# ESP32_MCU.net
KiCad netlist of a schematic drawn in Altium Designer
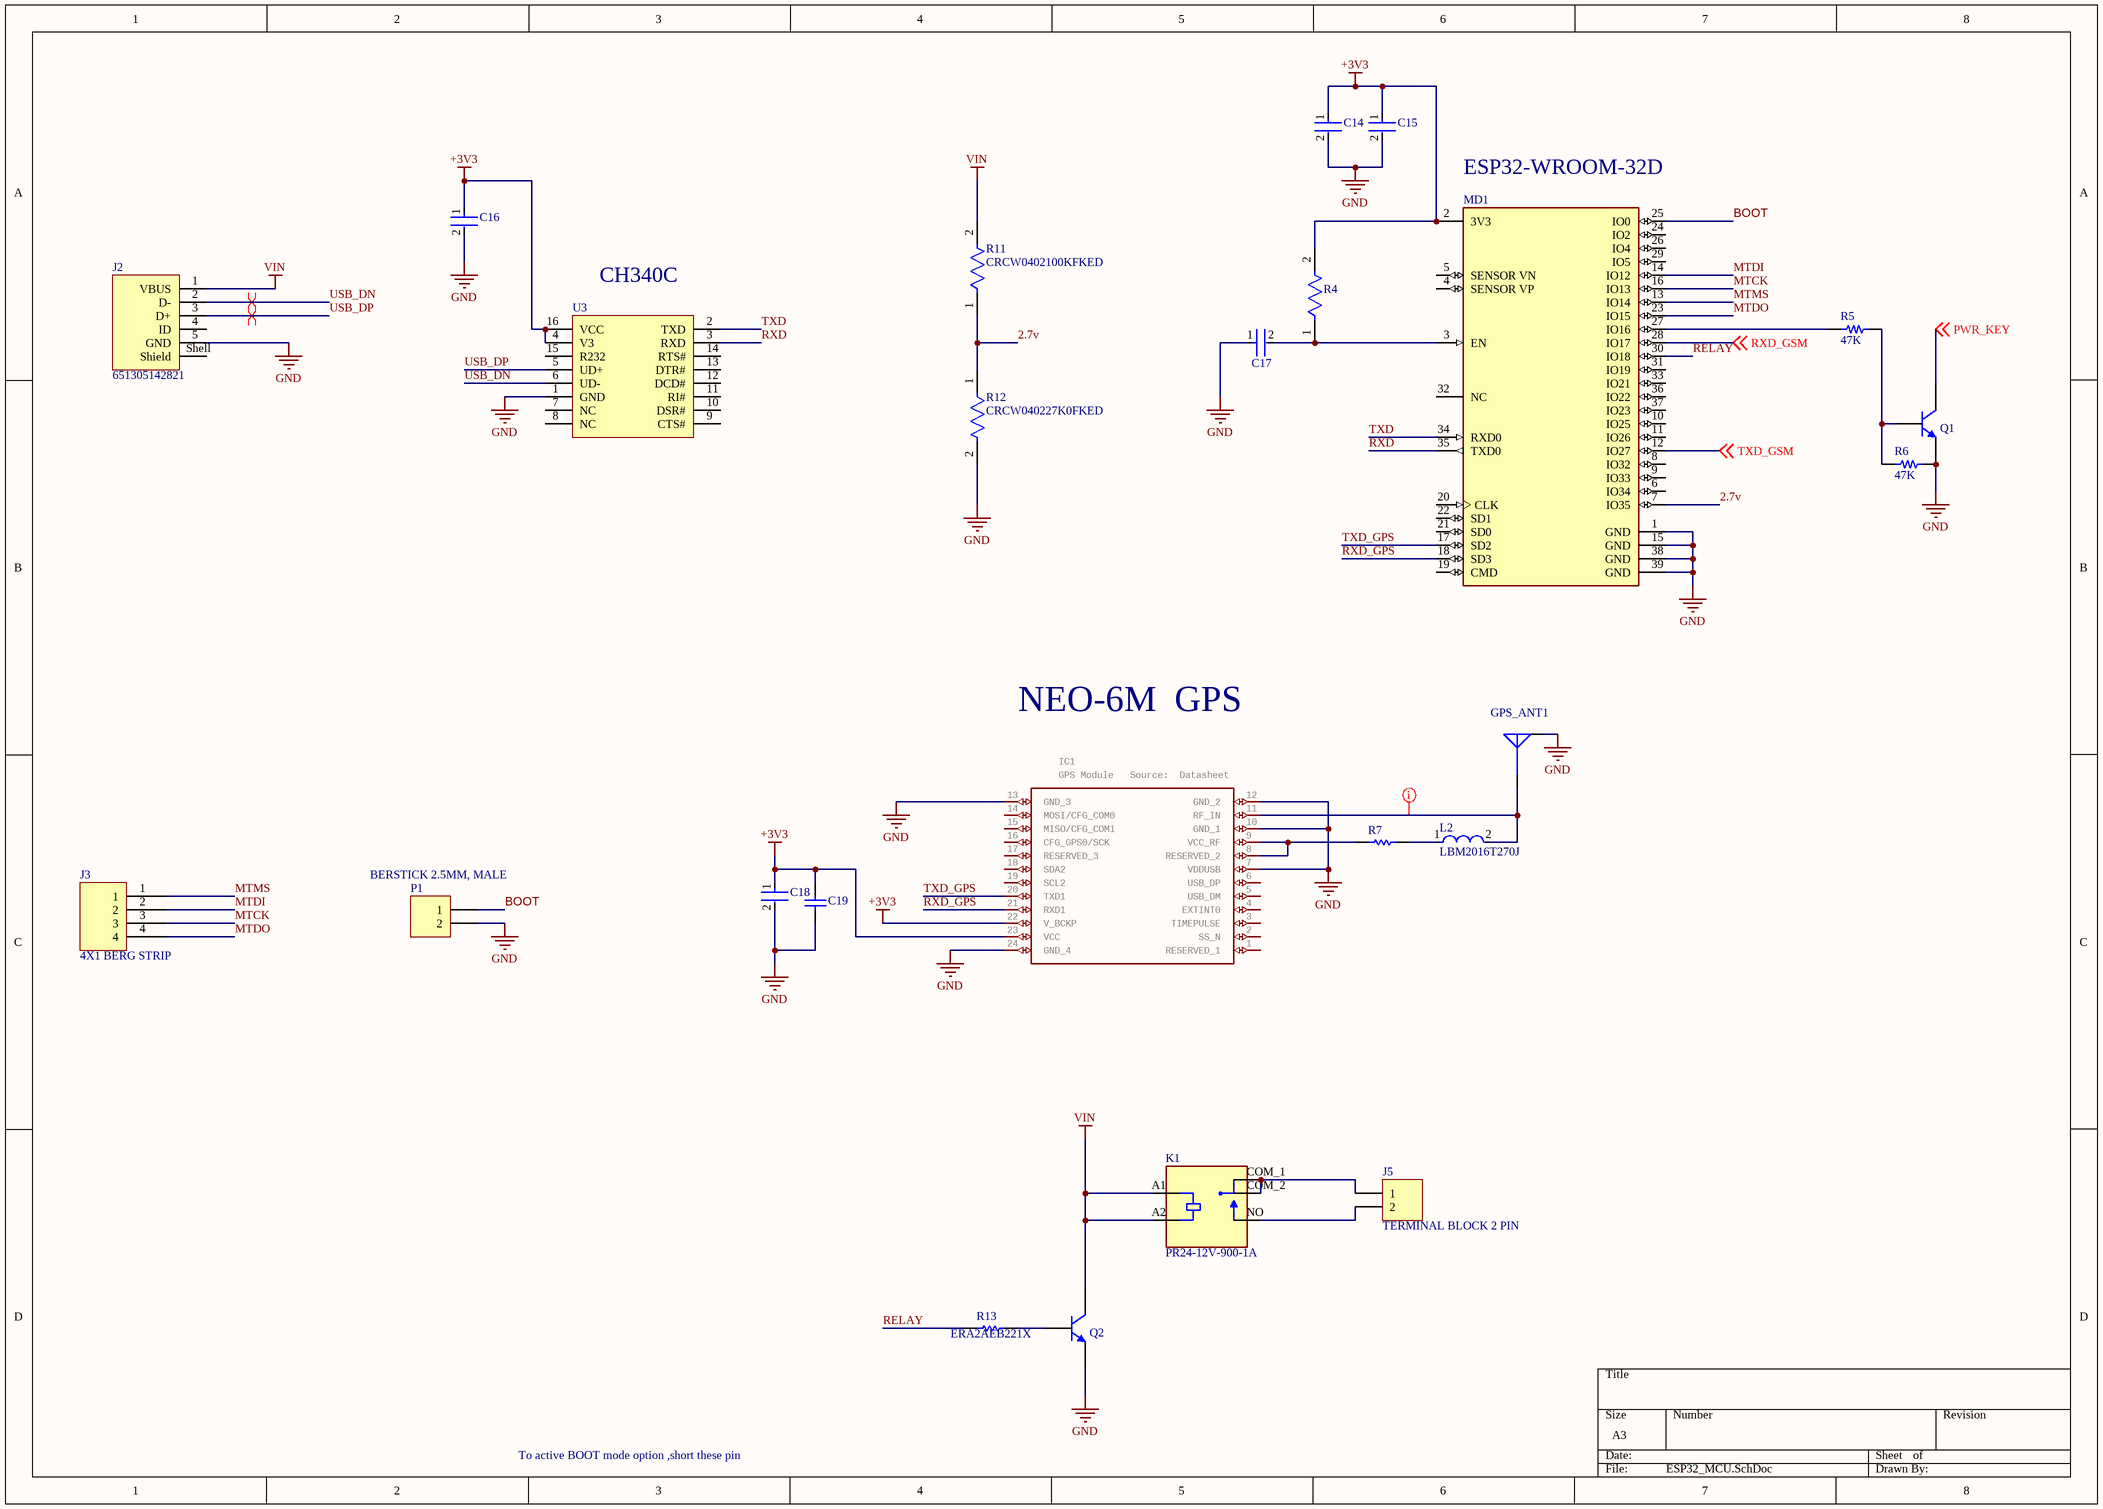
[diagram p0: ESP32_MCU.SchDoc]

(export (version "E")
  (design (tool "Eeschema 10.0.6"))
  (components
    (comp (ref "C14")
      (value "C0402C104K8RACTU")
      (footprint "FP-C0402-BB-MFG")
      (description "CAP CER 0.1UF 10V X7R 0402")
      (fields
        (field (name "OCTOPART") "https://octopart.com/c0402c104k8ractu-kemet-106349")
        (field (name "TOLERANCE") "0.1")
      )
      (libsource (lib "Altium Content Vault") (part "b4654b650e69147ec39a6b967a45e02"))
    )
    (comp (ref "C15")
      (value "C0402C106M9PACTU")
      (footprint "FP-C0402C106M9PACTU-MFG")
      (description "CAP CER 10UF 6.3V X5R 0402")
      (fields (field (name "TOLERANCE") "20%"))
      (libsource (lib "Altium Content Vault") (part "b4654b650e69147ec39a6b967a45e02"))
    )
    (comp (ref "C16")
      (value "C0402C104K8RACTU")
      (footprint "FP-C0402-BB-MFG")
      (description "CAP CER 0.1UF 10V X7R 0402")
      (fields
        (field (name "OCTOPART") "https://octopart.com/c0402c104k8ractu-kemet-106349")
        (field (name "TOLERANCE") "0.1")
      )
      (libsource (lib "Altium Content Vault") (part "b4654b650e69147ec39a6b967a45e02"))
    )
    (comp (ref "C17")
      (value "CC0402KRX5R5BB105")
      (footprint "FP-CC0402-MFG")
      (description "CAP CER 1UF 6.3V X5R 0402")
      (fields
        (field (name "MANUFACTURER") "YAGEO")
        (field (name "OCTOPART") "https://octopart.com/cc0402krx5r5bb105-yageo-42244618")
      )
      (libsource (lib "Altium Content Vault") (part "11868f565c42a9108669ba33697ecf6"))
    )
    (comp (ref "C18")
      (value "C0402C104K8RACTU")
      (footprint "FP-C0402-BB-MFG")
      (description "CAP CER 0.1UF 10V X7R 0402")
      (fields
        (field (name "OCTOPART") "https://octopart.com/c0402c104k8ractu-kemet-106349")
        (field (name "TOLERANCE") "0.1")
      )
      (libsource (lib "Altium Content Vault") (part "b4654b650e69147ec39a6b967a45e02"))
    )
    (comp (ref "C19")
      (value "C0402C475M7PACTU")
      (footprint "CAPC1005X60X30ML05T10")
      (fields (field (name "MANUFACTURER") "Kemet"))
      (libsource (lib "Altium Content Vault") (part "CAP"))
    )
    (comp (ref "GPS_ANT1")
      (value "UFL")
      (footprint "MOLEX SD-734120110")
      (fields (field (name "PARTNUMBER") "MOLEX SD-734120110"))
      (libsource (lib "GSM Shutter lock system") (part "UFL MOLEX SD-734120110"))
    )
    (comp (ref "IC1")
      (value "GPS Module   Source:  Datasheet")
      (footprint "NEO6M0001")
      (fields (field (name "MANUFACTURER_PART_NUMBER") "NEO-6M-0-001"))
      (libsource (lib "NEO-6M-0-001") (part "NEO-6M-0-001"))
    )
    (comp (ref "J2")
      (value "651305142821")
      (footprint "651305142821")
      (libsource (lib "Altium Content Vault") (part "Mini USB 2.0_Type AB_Receptacle_1 Port"))
    )
    (comp (ref "J3")
      (value "4X1 BERG STRIP")
      (footprint "CON4_100_40D72_TH_ST_MALE")
      (description "4 Pins, 1 Row 2.54mm Pitch, Straight bergstrip, Male")
      (fields (field (name "MANUFACTURER") "NA"))
      (libsource (lib "ESTEEMPCBLIB") (part "CON-BS-PLG_4X1-100-ST-TH"))
    )
    (comp (ref "J5")
      (value "TERMINAL BLOCK 2 PIN")
      (footprint "CON2_P196_1729128_TH_ST")
      (description "2 Pins, 1 Row 5mm Pitch, straight Connector, male")
      (fields
        (field (name "MANUFACTURER") "Phoenix Contact")
        (field (name "MANUFACTURER PART NUMBER") "MKDSN1,5/2")
      )
      (libsource (lib "ESTEEMPCBLIB") (part "CON-TB_2X1-196-ST-TH"))
    )
    (comp (ref "K1")
      (value "PR24-12V-900-1A")
      (footprint "RELAY_PR24-12V-900-1A")
      (description "27.4 x 31.8 x 20 mm, 12 V, 40 A, SPST (1 Form A), Power Relay")
      (fields (field (name "MF") "CUI Devices"))
      (libsource (lib "PR24-12V-900-1A") (part "PR24-12V-900-1A"))
    )
    (comp (ref "L2")
      (value "LBM2016T270J")
      (footprint "FP-LBM2016-1_6-0_2-IPC_C")
      (description "SMD Inductors 27uH ±5% 0.13A 4.16Ω 0806")
      (fields (field (name "TOLERANCE") "5%"))
      (libsource (lib "Altium Content Vault") (part "725321dda6339637d4d059423bc1c3c"))
    )
    (comp (ref "MD1")
      (value "ESP32-WROOM-32D")
      (footprint "FP-ESP32-WROOM-32D-MFG")
      (description "WIFI MODULE 32MBITS SPI FLASH")
      (fields
        (field (name "OCTOPART") "https://octopart.com/esp32-wroom-32d-espressif+systems-91040050")
        (field (name "MANUFACTURER") "Espressif Systems")
      )
      (libsource (lib "Altium Content Vault") (part "a031a76f8c27026a7a7f4657ff233a3"))
    )
    (comp (ref "P1")
      (value "BERSTICK 2.5MM, MALE")
      (footprint "CON2_100_43D62_TH_ST")
      (description "2 Pins, 1 Row 2.54mm Pitch, Straight bergstrip, Male")
      (fields (field (name "MANUFACTURER PART NUMBER") "NA") (field (name "MANUFACTURER") "Samtec"))
      (libsource (lib "ESTEEMPCBLIB") (part "CON-BS-PLG_2X1-100-ST-TH"))
    )
    (comp (ref "Q1")
      (value "8050")
      (footprint "SOT-23-3 2.9X2.4MM P0.95MM")
      (description "Bipolar (BJT) Transistor NPN 25V 1.5A 100MHz 625mW Surface Mount SOT-23")
      (fields (field (name "PARTNUMBER") "MMSS8050-L-TP"))
      (libsource (lib "Transistor") (part "MMSS8050 (SMD)"))
    )
    (comp (ref "Q2")
      (value "8050")
      (footprint "SOT-23-3 2.9X2.4MM P0.95MM")
      (description "Bipolar (BJT) Transistor NPN 25V 1.5A 100MHz 625mW Surface Mount SOT-23")
      (fields (field (name "PARTNUMBER") "MMSS8050-L-TP"))
      (libsource (lib "Transistor") (part "MMSS8050 (SMD)"))
    )
    (comp (ref "R4")
      (value "CRCW040210K0JNED")
      (footprint "FP-CRCW0402-e3-IPC_B")
      (description "RES Thick Film, 10kΩ, 5%, 0.063W, 200ppm/°C, 0402")
      (fields (field (name "TOLERANCE") "5%"))
      (libsource (lib "Altium Content Vault") (part "1029c3af85768c4190bb7ad29bc67b5"))
    )
    (comp (ref "R5")
      (value "47K")
      (footprint "RES 0603_1608")
      (description "SMT Resistor")
      (libsource (lib "Resistor") (part "Res 0603"))
    )
    (comp (ref "R6")
      (value "47K")
      (footprint "RES 0603_1608")
      (description "SMT Resistor")
      (libsource (lib "Resistor") (part "Res 0603"))
    )
    (comp (ref "R7")
      (value "CRCW040222R0FKED")
      (footprint "RESC1005X40X25LL05T05")
      (fields (field (name "MANUFACTURER") "Vishay Dale"))
      (libsource (lib "Altium Content Vault") (part "RES"))
    )
    (comp (ref "R11")
      (value "CRCW0402100KFKED")
      (footprint "FP-CRCW0402-e3-IPC_C")
      (description "RES Thick Film, 100kΩ, 1%, 0.063W, 100ppm/°C, 0402")
      (fields (field (name "TOLERANCE") "1%"))
      (libsource (lib "Altium Content Vault") (part "1029c3af85768c4190bb7ad29bc67b5"))
    )
    (comp (ref "R12")
      (value "CRCW040227K0FKED")
      (footprint "FP-CRCW0402-e3-IPC_A")
      (description "RES Thick Film, 27kΩ, 1%, 0.063W, 100ppm/°C, 0402")
      (fields (field (name "TOLERANCE") "1%"))
      (libsource (lib "Altium Content Vault") (part "1029c3af85768c4190bb7ad29bc67b5"))
    )
    (comp (ref "R13")
      (value "ERA2AEB221X")
      (footprint "RESC1005X40X25LL10T10")
      (fields (field (name "MANUFACTURER") "Panasonic"))
      (libsource (lib "Altium Content Vault") (part "RES"))
    )
    (comp (ref "U3")
      (value "CH340C")
      (footprint "SOIC16_50_284_25X90_SMT")
      (description "USB Bridge, USB to UART USB 2.0 UART Interface")
      (fields (field (name "MANUFACTURER") "Olimex"))
      (libsource (lib "ESTEEMPCBLIB") (part "IC_CH340C"))
    )
  )
  (nets
    (net (code "1") (name "+3V3") (class "Default")
      (node (ref "C14") (pin "1") (pinfunction "1_1") (pintype "passive"))
      (node (ref "C15") (pin "1") (pinfunction "1_1") (pintype "passive"))
      (node (ref "C16") (pin "1") (pinfunction "1_1") (pintype "passive"))
      (node (ref "C18") (pin "1") (pinfunction "1_1") (pintype "passive"))
      (node (ref "C19") (pin "2") (pinfunction "2_2") (pintype "passive"))
      (node (ref "IC1") (pin "22") (pinfunction "V_BCKP_22") (pintype "bidirectional"))
      (node (ref "IC1") (pin "23") (pinfunction "VCC_23") (pintype "bidirectional"))
      (node (ref "MD1") (pin "2") (pinfunction "3V3_2") (pintype "power_in"))
      (node (ref "R4") (pin "2") (pinfunction "2_2") (pintype "passive"))
      (node (ref "U3") (pin "16") (pinfunction "VCC_16") (pintype "passive"))
      (node (ref "U3") (pin "4") (pinfunction "V3_4") (pintype "passive"))
    )
    (net (code "2") (name "/2.7v") (class "Default")
      (node (ref "MD1") (pin "7") (pinfunction "IO35_7") (pintype "bidirectional"))
      (node (ref "R11") (pin "1") (pinfunction "1_1") (pintype "passive"))
      (node (ref "R12") (pin "1") (pinfunction "1_1") (pintype "passive"))
    )
    (net (code "3") (name "/BOOT") (class "Default")
      (node (ref "MD1") (pin "25") (pinfunction "IO0_25") (pintype "bidirectional"))
      (node (ref "P1") (pin "1") (pinfunction "1_1") (pintype "passive"))
    )
    (net (code "4") (name "/MTCK") (class "Default")
      (node (ref "J3") (pin "3") (pinfunction "3_3") (pintype "passive"))
      (node (ref "MD1") (pin "16") (pinfunction "IO13_16") (pintype "bidirectional"))
    )
    (net (code "5") (name "/MTDI") (class "Default")
      (node (ref "J3") (pin "2") (pinfunction "2_2") (pintype "passive"))
      (node (ref "MD1") (pin "14") (pinfunction "IO12_14") (pintype "bidirectional"))
    )
    (net (code "6") (name "/MTDO") (class "Default")
      (node (ref "J3") (pin "4") (pinfunction "4_4") (pintype "passive"))
      (node (ref "MD1") (pin "23") (pinfunction "IO15_23") (pintype "bidirectional"))
    )
    (net (code "7") (name "/MTMS") (class "Default")
      (node (ref "J3") (pin "1") (pinfunction "1_1") (pintype "passive"))
      (node (ref "MD1") (pin "13") (pinfunction "IO14_13") (pintype "bidirectional"))
    )
    (net (code "8") (name "/RELAY") (class "Default")
      (node (ref "MD1") (pin "30") (pinfunction "IO18_30") (pintype "bidirectional"))
      (node (ref "R13") (pin "1") (pinfunction "1_1") (pintype "passive"))
    )
    (net (code "9") (name "/RXD") (class "Default")
      (node (ref "MD1") (pin "35") (pinfunction "TXD0_35") (pintype "output"))
      (node (ref "U3") (pin "3") (pinfunction "RXD_3") (pintype "passive"))
    )
    (net (code "10") (name "/RXD_GPS") (class "Default")
      (node (ref "IC1") (pin "21") (pinfunction "RXD1_21") (pintype "bidirectional"))
      (node (ref "MD1") (pin "18") (pinfunction "SD3_18") (pintype "bidirectional"))
    )
    (net (code "11") (name "/TXD") (class "Default")
      (node (ref "MD1") (pin "34") (pinfunction "RXD0_34") (pintype "input"))
      (node (ref "U3") (pin "2") (pinfunction "TXD_2") (pintype "passive"))
    )
    (net (code "12") (name "/TXD_GPS") (class "Default")
      (node (ref "IC1") (pin "20") (pinfunction "TXD1_20") (pintype "bidirectional"))
      (node (ref "MD1") (pin "17") (pinfunction "SD2_17") (pintype "bidirectional"))
    )
    (net (code "13") (name "/USB_DN") (class "Default")
      (node (ref "J2") (pin "2") (pinfunction "D-_2") (pintype "passive"))
      (node (ref "U3") (pin "6") (pinfunction "UD-_6") (pintype "passive"))
    )
    (net (code "14") (name "/USB_DP") (class "Default")
      (node (ref "J2") (pin "3") (pinfunction "D+_3") (pintype "passive"))
      (node (ref "U3") (pin "5") (pinfunction "UD+_5") (pintype "passive"))
    )
    (net (code "15") (name "GND") (class "Default")
      (node (ref "C14") (pin "2") (pinfunction "2_2") (pintype "passive"))
      (node (ref "C15") (pin "2") (pinfunction "2_2") (pintype "passive"))
      (node (ref "C16") (pin "2") (pinfunction "2_2") (pintype "passive"))
      (node (ref "C17") (pin "1") (pinfunction "1_1") (pintype "passive"))
      (node (ref "C18") (pin "2") (pinfunction "2_2") (pintype "passive"))
      (node (ref "C19") (pin "1") (pinfunction "1_1") (pintype "passive"))
      (node (ref "GPS_ANT1") (pin "G") (pinfunction "G_G") (pintype "passive"))
      (node (ref "IC1") (pin "10") (pinfunction "GND_1_10") (pintype "bidirectional"))
      (node (ref "IC1") (pin "12") (pinfunction "GND_2_12") (pintype "bidirectional"))
      (node (ref "IC1") (pin "13") (pinfunction "GND_3_13") (pintype "bidirectional"))
      (node (ref "IC1") (pin "24") (pinfunction "GND_4_24") (pintype "bidirectional"))
      (node (ref "IC1") (pin "7") (pinfunction "VDDUSB_7") (pintype "bidirectional"))
      (node (ref "J2") (pin "5") (pinfunction "GND_5") (pintype "passive"))
      (node (ref "MD1") (pin "1") (pinfunction "GND_1") (pintype "power_in"))
      (node (ref "MD1") (pin "15") (pinfunction "GND_15") (pintype "power_in"))
      (node (ref "MD1") (pin "38") (pinfunction "GND_38") (pintype "power_in"))
      (node (ref "MD1") (pin "39") (pinfunction "GND_39") (pintype "power_in"))
      (node (ref "P1") (pin "2") (pinfunction "2_2") (pintype "passive"))
      (node (ref "Q1") (pin "2") (pinfunction "E_2") (pintype "passive"))
      (node (ref "Q2") (pin "2") (pinfunction "E_2") (pintype "passive"))
      (node (ref "R12") (pin "2") (pinfunction "2_2") (pintype "passive"))
      (node (ref "R6") (pin "1") (pinfunction "1_1") (pintype "passive"))
      (node (ref "U3") (pin "1") (pinfunction "GND_1") (pintype "passive"))
    )
    (net (code "16") (name "Net-(IC1-RESERVED_2)") (class "Default")
      (node (ref "IC1") (pin "8") (pinfunction "RESERVED_2_8") (pintype "bidirectional"))
      (node (ref "IC1") (pin "9") (pinfunction "VCC_RF_9") (pintype "bidirectional"))
      (node (ref "R7") (pin "1") (pinfunction "1_1") (pintype "passive"))
    )
    (net (code "17") (name "Net-(IC1-RF_IN)") (class "Default")
      (node (ref "GPS_ANT1") (pin "S") (pinfunction "S_S") (pintype "passive"))
      (node (ref "IC1") (pin "11") (pinfunction "RF_IN_11") (pintype "bidirectional"))
      (node (ref "L2") (pin "2") (pinfunction "2_2") (pintype "passive"))
    )
    (net (code "18") (name "Net-(J5-Pad2)") (class "Default")
      (node (ref "J5") (pin "2") (pinfunction "2_2") (pintype "passive"))
      (node (ref "K1") (pin "NO") (pinfunction "NO_NO") (pintype "passive"))
    )
    (net (code "19") (name "Net-(K1-COM1)") (class "Default")
      (node (ref "J5") (pin "1") (pinfunction "1_1") (pintype "passive"))
      (node (ref "K1") (pin "COM_1") (pinfunction "COM1_COM_1") (pintype "passive"))
      (node (ref "K1") (pin "COM_2") (pinfunction "COM2_COM_2") (pintype "passive"))
    )
    (net (code "20") (name "Net-(L2-Pad1)") (class "Default")
      (node (ref "L2") (pin "1") (pinfunction "1_1") (pintype "passive"))
      (node (ref "R7") (pin "2") (pinfunction "2_2") (pintype "passive"))
    )
    (net (code "21") (name "Net-(MD1-EN)") (class "Default")
      (node (ref "C17") (pin "2") (pinfunction "2_2") (pintype "passive"))
      (node (ref "MD1") (pin "3") (pinfunction "EN_3") (pintype "input"))
      (node (ref "R4") (pin "1") (pinfunction "1_1") (pintype "passive"))
    )
    (net (code "22") (name "Net-(MD1-IO16)") (class "Default")
      (node (ref "MD1") (pin "27") (pinfunction "IO16_27") (pintype "bidirectional"))
      (node (ref "R5") (pin "2") (pinfunction "2_2") (pintype "passive"))
    )
    (net (code "23") (name "Net-(Q1-B)") (class "Default")
      (node (ref "Q1") (pin "1") (pinfunction "B_1") (pintype "passive"))
      (node (ref "R5") (pin "1") (pinfunction "1_1") (pintype "passive"))
      (node (ref "R6") (pin "2") (pinfunction "2_2") (pintype "passive"))
    )
    (net (code "24") (name "Net-(Q2-B)") (class "Default")
      (node (ref "Q2") (pin "1") (pinfunction "B_1") (pintype "passive"))
      (node (ref "R13") (pin "2") (pinfunction "2_2") (pintype "passive"))
    )
    (net (code "25") (name "PWR_KEY") (class "Default")
      (node (ref "Q1") (pin "3") (pinfunction "C_3") (pintype "passive"))
    )
    (net (code "26") (name "RXD_GSM") (class "Default")
      (node (ref "MD1") (pin "28") (pinfunction "IO17_28") (pintype "bidirectional"))
    )
    (net (code "27") (name "TXD_GSM") (class "Default")
      (node (ref "MD1") (pin "12") (pinfunction "IO27_12") (pintype "bidirectional"))
    )
    (net (code "28") (name "VIN") (class "Default")
      (node (ref "J2") (pin "1") (pinfunction "VBUS_1") (pintype "passive"))
      (node (ref "K1") (pin "A1") (pinfunction "COIL1_A1") (pintype "passive"))
      (node (ref "K1") (pin "A2") (pinfunction "COIL2_A2") (pintype "passive"))
      (node (ref "Q2") (pin "3") (pinfunction "C_3") (pintype "passive"))
      (node (ref "R11") (pin "2") (pinfunction "2_2") (pintype "passive"))
    )
    (net (code "29") (name "unconnected-(IC1-CFG_GPS0{slash}SCK-Pad16)") (class "Default")
      (node (ref "IC1") (pin "16") (pinfunction "CFG_GPS0/SCK_16") (pintype "bidirectional"))
    )
    (net (code "30") (name "unconnected-(IC1-EXTINT0-Pad4)") (class "Default")
      (node (ref "IC1") (pin "4") (pinfunction "EXTINT0_4") (pintype "bidirectional"))
    )
    (net (code "31") (name "unconnected-(IC1-MISO{slash}CFG_COM1-Pad15)") (class "Default")
      (node (ref "IC1") (pin "15") (pinfunction "MISO/CFG_COM1_15") (pintype "bidirectional"))
    )
    (net (code "32") (name "unconnected-(IC1-MOSI{slash}CFG_COM0-Pad14)") (class "Default")
      (node (ref "IC1") (pin "14") (pinfunction "MOSI/CFG_COM0_14") (pintype "bidirectional"))
    )
    (net (code "33") (name "unconnected-(IC1-RESERVED_1-Pad1)") (class "Default")
      (node (ref "IC1") (pin "1") (pinfunction "RESERVED_1_1") (pintype "bidirectional"))
    )
    (net (code "34") (name "unconnected-(IC1-RESERVED_3-Pad17)") (class "Default")
      (node (ref "IC1") (pin "17") (pinfunction "RESERVED_3_17") (pintype "bidirectional"))
    )
    (net (code "35") (name "unconnected-(IC1-SCL2-Pad19)") (class "Default")
      (node (ref "IC1") (pin "19") (pinfunction "SCL2_19") (pintype "bidirectional"))
    )
    (net (code "36") (name "unconnected-(IC1-SDA2-Pad18)") (class "Default")
      (node (ref "IC1") (pin "18") (pinfunction "SDA2_18") (pintype "bidirectional"))
    )
    (net (code "37") (name "unconnected-(IC1-SS_N-Pad2)") (class "Default")
      (node (ref "IC1") (pin "2") (pinfunction "SS_N_2") (pintype "bidirectional"))
    )
    (net (code "38") (name "unconnected-(IC1-TIMEPULSE-Pad3)") (class "Default")
      (node (ref "IC1") (pin "3") (pinfunction "TIMEPULSE_3") (pintype "bidirectional"))
    )
    (net (code "39") (name "unconnected-(IC1-USB_DM-Pad5)") (class "Default")
      (node (ref "IC1") (pin "5") (pinfunction "USB_DM_5") (pintype "bidirectional"))
    )
    (net (code "40") (name "unconnected-(IC1-USB_DP-Pad6)") (class "Default")
      (node (ref "IC1") (pin "6") (pinfunction "USB_DP_6") (pintype "bidirectional"))
    )
    (net (code "41") (name "unconnected-(J2-ID-Pad4)") (class "Default")
      (node (ref "J2") (pin "4") (pinfunction "ID_4") (pintype "passive"))
    )
    (net (code "42") (name "unconnected-(J2-Shield-PadShell)") (class "Default")
      (node (ref "J2") (pin "Shell") (pinfunction "Shield_Shell") (pintype "passive"))
    )
    (net (code "43") (name "unconnected-(MD1-CLK-Pad20)") (class "Default")
      (node (ref "MD1") (pin "20") (pinfunction "CLK_20") (pintype "input"))
    )
    (net (code "44") (name "unconnected-(MD1-CMD-Pad19)") (class "Default")
      (node (ref "MD1") (pin "19") (pinfunction "CMD_19") (pintype "bidirectional"))
    )
    (net (code "45") (name "unconnected-(MD1-IO2-Pad24)") (class "Default")
      (node (ref "MD1") (pin "24") (pinfunction "IO2_24") (pintype "bidirectional"))
    )
    (net (code "46") (name "unconnected-(MD1-IO4-Pad26)") (class "Default")
      (node (ref "MD1") (pin "26") (pinfunction "IO4_26") (pintype "bidirectional"))
    )
    (net (code "47") (name "unconnected-(MD1-IO5-Pad29)") (class "Default")
      (node (ref "MD1") (pin "29") (pinfunction "IO5_29") (pintype "bidirectional"))
    )
    (net (code "48") (name "unconnected-(MD1-IO19-Pad31)") (class "Default")
      (node (ref "MD1") (pin "31") (pinfunction "IO19_31") (pintype "bidirectional"))
    )
    (net (code "49") (name "unconnected-(MD1-IO21-Pad33)") (class "Default")
      (node (ref "MD1") (pin "33") (pinfunction "IO21_33") (pintype "bidirectional"))
    )
    (net (code "50") (name "unconnected-(MD1-IO22-Pad36)") (class "Default")
      (node (ref "MD1") (pin "36") (pinfunction "IO22_36") (pintype "bidirectional"))
    )
    (net (code "51") (name "unconnected-(MD1-IO23-Pad37)") (class "Default")
      (node (ref "MD1") (pin "37") (pinfunction "IO23_37") (pintype "bidirectional"))
    )
    (net (code "52") (name "unconnected-(MD1-IO25-Pad10)") (class "Default")
      (node (ref "MD1") (pin "10") (pinfunction "IO25_10") (pintype "bidirectional"))
    )
    (net (code "53") (name "unconnected-(MD1-IO26-Pad11)") (class "Default")
      (node (ref "MD1") (pin "11") (pinfunction "IO26_11") (pintype "bidirectional"))
    )
    (net (code "54") (name "unconnected-(MD1-IO32-Pad8)") (class "Default")
      (node (ref "MD1") (pin "8") (pinfunction "IO32_8") (pintype "bidirectional"))
    )
    (net (code "55") (name "unconnected-(MD1-IO33-Pad9)") (class "Default")
      (node (ref "MD1") (pin "9") (pinfunction "IO33_9") (pintype "bidirectional"))
    )
    (net (code "56") (name "unconnected-(MD1-IO34-Pad6)") (class "Default")
      (node (ref "MD1") (pin "6") (pinfunction "IO34_6") (pintype "bidirectional"))
    )
    (net (code "57") (name "unconnected-(MD1-NC-Pad32)") (class "Default")
      (node (ref "MD1") (pin "32") (pinfunction "NC_32") (pintype "passive"))
    )
    (net (code "58") (name "unconnected-(MD1-SD0-Pad21)") (class "Default")
      (node (ref "MD1") (pin "21") (pinfunction "SD0_21") (pintype "bidirectional"))
    )
    (net (code "59") (name "unconnected-(MD1-SD1-Pad22)") (class "Default")
      (node (ref "MD1") (pin "22") (pinfunction "SD1_22") (pintype "bidirectional"))
    )
    (net (code "60") (name "unconnected-(MD1-SENSOR_VN-Pad5)") (class "Default")
      (node (ref "MD1") (pin "5") (pinfunction "SENSOR_VN_5") (pintype "bidirectional"))
    )
    (net (code "61") (name "unconnected-(MD1-SENSOR_VP-Pad4)") (class "Default")
      (node (ref "MD1") (pin "4") (pinfunction "SENSOR_VP_4") (pintype "bidirectional"))
    )
    (net (code "62") (name "unconnected-(U3-CTS#-Pad9)") (class "Default")
      (node (ref "U3") (pin "9") (pinfunction "CTS#_9") (pintype "passive"))
    )
    (net (code "63") (name "unconnected-(U3-DCD#-Pad12)") (class "Default")
      (node (ref "U3") (pin "12") (pinfunction "DCD#_12") (pintype "passive"))
    )
    (net (code "64") (name "unconnected-(U3-DSR#-Pad10)") (class "Default")
      (node (ref "U3") (pin "10") (pinfunction "DSR#_10") (pintype "passive"))
    )
    (net (code "65") (name "unconnected-(U3-DTR#-Pad13)") (class "Default")
      (node (ref "U3") (pin "13") (pinfunction "DTR#_13") (pintype "passive"))
    )
    (net (code "66") (name "unconnected-(U3-NC-Pad7)") (class "Default")
      (node (ref "U3") (pin "7") (pinfunction "NC_7") (pintype "passive"))
    )
    (net (code "67") (name "unconnected-(U3-NC-Pad8)") (class "Default")
      (node (ref "U3") (pin "8") (pinfunction "NC_8") (pintype "passive"))
    )
    (net (code "68") (name "unconnected-(U3-R232-Pad15)") (class "Default")
      (node (ref "U3") (pin "15") (pinfunction "R232_15") (pintype "passive"))
    )
    (net (code "69") (name "unconnected-(U3-RI#-Pad11)") (class "Default")
      (node (ref "U3") (pin "11") (pinfunction "RI#_11") (pintype "passive"))
    )
    (net (code "70") (name "unconnected-(U3-RTS#-Pad14)") (class "Default")
      (node (ref "U3") (pin "14") (pinfunction "RTS#_14") (pintype "passive"))
    )
  )
)
